# 03_-_Power.net
KiCad netlist of a schematic drawn in Altium Designer
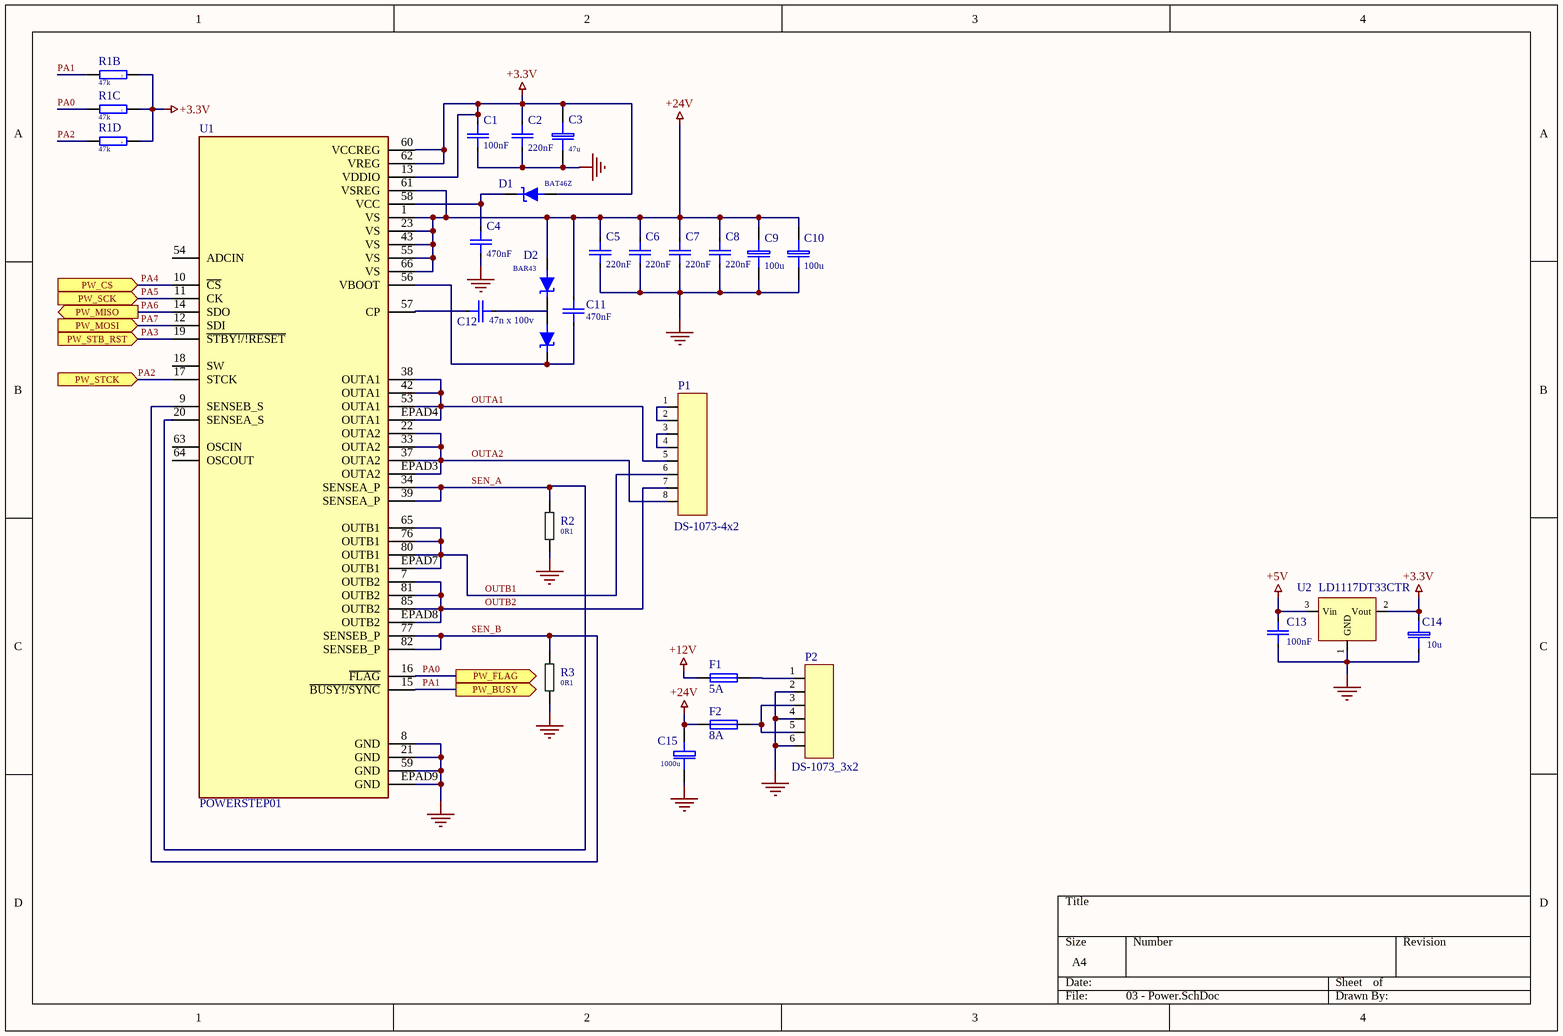
[diagram p0: 03 - Power.SchDoc]

(export (version "E")
  (design (tool "Eeschema 10.0.6"))
  (components
    (comp (ref "C1")
      (value "100nF")
      (footprint "CAP: 0805")
      (description "SMD-0805")
      (libsource (lib "RCL_SMD_Integrated_Library") (part "C-0805"))
    )
    (comp (ref "C2")
      (value "220nF")
      (footprint "CAP: 0805")
      (description "SMD-0805")
      (libsource (lib "RCL_SMD_Integrated_Library") (part "C-0805"))
    )
    (comp (ref "C3")
      (value "47u")
      (footprint "EL SMD Case C D5x5.3 h5.4(0505)")
      (description "EL 50V SMD Case C D5x5.3 h5.4")
      (libsource (lib "SMD-RCL") (part "EL 10u/50V"))
    )
    (comp (ref "C4")
      (value "470nF")
      (footprint "CAP: 0805")
      (description "SMD-0805")
      (libsource (lib "RCL_SMD_Integrated_Library") (part "C-0805"))
    )
    (comp (ref "C5")
      (value "220nF")
      (footprint "CAP: 0805")
      (description "SMD-0805")
      (libsource (lib "RCL_SMD_Integrated_Library") (part "C-0805"))
    )
    (comp (ref "C6")
      (value "220nF")
      (footprint "CAP: 0805")
      (description "SMD-0805")
      (libsource (lib "RCL_SMD_Integrated_Library") (part "C-0805"))
    )
    (comp (ref "C7")
      (value "220nF")
      (footprint "CAP: 0805")
      (description "SMD-0805")
      (libsource (lib "RCL_SMD_Integrated_Library") (part "C-0805"))
    )
    (comp (ref "C8")
      (value "220nF")
      (footprint "CAP: 0805")
      (description "SMD-0805")
      (libsource (lib "RCL_SMD_Integrated_Library") (part "C-0805"))
    )
    (comp (ref "C9")
      (value "100u")
      (footprint "EL SMD Case G D10x10.3 h10.2(1010)")
      (description "EL 35V SMD Case G D10x10.3h10.5")
      (libsource (lib "SMD-RCL") (part "EL 100u/35V"))
    )
    (comp (ref "C10")
      (value "100u")
      (footprint "EL SMD Case G D10x10.3 h10.2(1010)")
      (description "EL 35V SMD Case G D10x10.3h10.5")
      (libsource (lib "SMD-RCL") (part "EL 100u/35V"))
    )
    (comp (ref "C11")
      (value "470nF")
      (footprint "CAP: 0805")
      (description "SMD-0805")
      (libsource (lib "RCL_SMD_Integrated_Library") (part "C-0805"))
    )
    (comp (ref "C12")
      (value "47n x 100v")
      (footprint "CAP: 0805")
      (description "SMD-0805")
      (libsource (lib "RCL_SMD_Integrated_Library") (part "C-0805"))
    )
    (comp (ref "C13")
      (value "100nF")
      (footprint "CAP: 0805")
      (description "SMD-0805")
      (libsource (lib "RCL_SMD_Integrated_Library") (part "C-0805"))
    )
    (comp (ref "C14")
      (value "10u")
      (footprint "EL Case A (3216-18)")
      (description "El Case A (2012-12)")
      (libsource (lib "RCL_SMD_Integrated_Library") (part "EL 10u/16V Tant."))
    )
    (comp (ref "C15")
      (value "1000u")
      (footprint "El-d13-h21-F5.08")
      (description "35V 105C 34m 1.8A 5000h")
      (libsource (lib "Cap-El") (part "1000u-35V 105F"))
    )
    (comp (ref "D1")
      (value "BAT46Z")
      (footprint "SOD123")
      (description "SMD-SOT123 60V 15mA 2.2pF 1nS")
      (libsource (lib "Diodes") (part "1N6263"))
    )
    (comp (ref "D2")
      (value "BAR43")
      (footprint "SOT23")
      (description "SMD-SOT23 30V 0.2A 5nS 10pF")
      (libsource (lib "Diodes") (part "BAT54S"))
    )
    (comp (ref "F1")
      (value "5A")
      (footprint "Littelfuse 0451/453")
      (description "0451003")
      (libsource (lib "stm32_Integrated_Library") (part "Littelfuse 0451"))
    )
    (comp (ref "F2")
      (value "8A")
      (footprint "Littelfuse 0451/453")
      (description "0451003")
      (libsource (lib "stm32_Integrated_Library") (part "Littelfuse 0451"))
    )
    (comp (ref "P1")
      (value "DS-1073-4x2")
      (footprint "DS-1073-4x2")
      (libsource (lib "stm32_Integrated_Library") (part "DS-1073-4x2"))
    )
    (comp (ref "P2")
      (value "DS-1073_3x2")
      (footprint "DS-1073-2x3")
      (libsource (lib "stm32_Integrated_Library") (part "DS-1073_3x2"))
    )
    (comp (ref "R1")
      (value "47k")
      (footprint "RM4x0603")
      (description "SMD 4RM-0603 1\\16W 5%")
      (libsource (lib "SMD-RCL") (part "4RM-0603"))
    )
    (comp (ref "R2")
      (value "0R1")
      (footprint "R2512")
      (description "SMD 2512 1W 5% 200V")
      (libsource (lib "SMD-RCL") (part "R-2512"))
    )
    (comp (ref "R3")
      (value "0R1")
      (footprint "R2512")
      (description "SMD 2512 1W 5% 200V")
      (libsource (lib "SMD-RCL") (part "R-2512"))
    )
    (comp (ref "U1")
      (value "POWERSTEP01")
      (footprint "POWERSTEP01")
      (description "Bipolar Motor Driver Power MOSFET SPI 89-VFQFPN _11x14_")
      (fields (field (name "MF") "STMicroelectronics"))
      (libsource (lib "stm32_Integrated_Library") (part "POWERSTEP01"))
    )
    (comp (ref "U2")
      (value "LD1117DT33CTR")
      (footprint "DPAK")
      (libsource (lib "stm32_Integrated_Library") (part "LD1117DT33CTR"))
    )
  )
  (nets
    (net (code "1") (name "+3.3V") (class "Default")
      (node (ref "C1") (pin "2") (pinfunction "2_2") (pintype "passive"))
      (node (ref "C14") (pin "1") (pinfunction "1_1") (pintype "passive"))
      (node (ref "C2") (pin "1") (pinfunction "1_1") (pintype "passive"))
      (node (ref "C3") (pin "1") (pinfunction "+_1") (pintype "passive"))
      (node (ref "D1") (pin "1") (pinfunction "A_1") (pintype "passive"))
      (node (ref "R1") (pin "2") (pinfunction "2_2") (pintype "passive"))
      (node (ref "R1") (pin "3") (pinfunction "3_3") (pintype "passive"))
      (node (ref "R1") (pin "4") (pinfunction "4_4") (pintype "passive"))
      (node (ref "U1") (pin "13") (pinfunction "VDDIO_13") (pintype "power_in"))
      (node (ref "U1") (pin "60") (pinfunction "VCCREG_60") (pintype "power_in"))
      (node (ref "U1") (pin "62") (pinfunction "VREG_62") (pintype "power_in"))
      (node (ref "U2") (pin "2") (pinfunction "Vout_2") (pintype "passive"))
    )
    (net (code "2") (name "+5V") (class "Default")
      (node (ref "C13") (pin "2") (pinfunction "2_2") (pintype "passive"))
      (node (ref "U2") (pin "3") (pinfunction "Vin_3") (pintype "passive"))
    )
    (net (code "3") (name "+12V") (class "Default")
      (node (ref "F1") (pin "1") (pinfunction "1_1") (pintype "passive"))
    )
    (net (code "4") (name "+24V") (class "Default")
      (node (ref "C10") (pin "1") (pinfunction "1_1") (pintype "passive"))
      (node (ref "C11") (pin "1") (pinfunction "1_1") (pintype "passive"))
      (node (ref "C15") (pin "1") (pinfunction "1_1") (pintype "passive"))
      (node (ref "C5") (pin "1") (pinfunction "1_1") (pintype "passive"))
      (node (ref "C6") (pin "1") (pinfunction "1_1") (pintype "passive"))
      (node (ref "C7") (pin "1") (pinfunction "1_1") (pintype "passive"))
      (node (ref "C8") (pin "1") (pinfunction "1_1") (pintype "passive"))
      (node (ref "C9") (pin "1") (pinfunction "1_1") (pintype "passive"))
      (node (ref "D2") (pin "1") (pinfunction "1_1") (pintype "passive"))
      (node (ref "F2") (pin "1") (pinfunction "1_1") (pintype "passive"))
      (node (ref "U1") (pin "1") (pinfunction "VS_1") (pintype "passive"))
      (node (ref "U1") (pin "23") (pinfunction "VS_23") (pintype "passive"))
      (node (ref "U1") (pin "43") (pinfunction "VS_43") (pintype "passive"))
      (node (ref "U1") (pin "55") (pinfunction "VS_55") (pintype "passive"))
      (node (ref "U1") (pin "61") (pinfunction "VSREG_61") (pintype "passive"))
      (node (ref "U1") (pin "66") (pinfunction "VS_66") (pintype "passive"))
    )
    (net (code "5") (name "/OUTA1") (class "Default")
      (node (ref "P1") (pin "5") (pintype "passive"))
      (node (ref "U1") (pin "38") (pinfunction "OUTA1_38") (pintype "power_in"))
      (node (ref "U1") (pin "42") (pinfunction "OUTA1_42") (pintype "power_in"))
      (node (ref "U1") (pin "53") (pinfunction "OUTA1_53") (pintype "power_in"))
      (node (ref "U1") (pin "EPAD4") (pinfunction "OUTA1_EPAD4") (pintype "power_in"))
    )
    (net (code "6") (name "/OUTA2") (class "Default")
      (node (ref "P1") (pin "8") (pintype "passive"))
      (node (ref "U1") (pin "22") (pinfunction "OUTA2_22") (pintype "power_in"))
      (node (ref "U1") (pin "33") (pinfunction "OUTA2_33") (pintype "power_in"))
      (node (ref "U1") (pin "37") (pinfunction "OUTA2_37") (pintype "power_in"))
      (node (ref "U1") (pin "EPAD3") (pinfunction "OUTA2_EPAD3") (pintype "power_in"))
    )
    (net (code "7") (name "/OUTB1") (class "Default")
      (node (ref "P1") (pin "6") (pintype "passive"))
      (node (ref "U1") (pin "65") (pinfunction "OUTB1_65") (pintype "power_in"))
      (node (ref "U1") (pin "76") (pinfunction "OUTB1_76") (pintype "power_in"))
      (node (ref "U1") (pin "80") (pinfunction "OUTB1_80") (pintype "power_in"))
      (node (ref "U1") (pin "EPAD7") (pinfunction "OUTB1_EPAD7") (pintype "power_in"))
    )
    (net (code "8") (name "/OUTB2") (class "Default")
      (node (ref "P1") (pin "7") (pintype "passive"))
      (node (ref "U1") (pin "7") (pinfunction "OUTB2_7") (pintype "power_in"))
      (node (ref "U1") (pin "81") (pinfunction "OUTB2_81") (pintype "power_in"))
      (node (ref "U1") (pin "85") (pinfunction "OUTB2_85") (pintype "power_in"))
      (node (ref "U1") (pin "EPAD8") (pinfunction "OUTB2_EPAD8") (pintype "power_in"))
    )
    (net (code "9") (name "/PA0") (class "Default")
      (node (ref "R1") (pin "6") (pinfunction "6_6") (pintype "passive"))
      (node (ref "U1") (pin "16") (pinfunction "~{FLAG}_16") (pintype "passive"))
    )
    (net (code "10") (name "/PA1") (class "Default")
      (node (ref "R1") (pin "7") (pinfunction "7_7") (pintype "passive"))
      (node (ref "U1") (pin "15") (pinfunction "~{BUSY!/SYNC}_15") (pintype "passive"))
    )
    (net (code "11") (name "/PA2") (class "Default")
      (node (ref "R1") (pin "5") (pinfunction "5_5") (pintype "passive"))
      (node (ref "U1") (pin "17") (pinfunction "STCK_17") (pintype "passive"))
    )
    (net (code "12") (name "/PA3") (class "Default")
      (node (ref "U1") (pin "19") (pinfunction "~{STBY!/!RESET}_19") (pintype "passive"))
    )
    (net (code "13") (name "/PA4") (class "Default")
      (node (ref "U1") (pin "10") (pinfunction "~{CS}_10") (pintype "passive"))
    )
    (net (code "14") (name "/PA5") (class "Default")
      (node (ref "U1") (pin "11") (pinfunction "CK_11") (pintype "passive"))
    )
    (net (code "15") (name "/PA6") (class "Default")
      (node (ref "U1") (pin "14") (pinfunction "SDO_14") (pintype "passive"))
    )
    (net (code "16") (name "/PA7") (class "Default")
      (node (ref "U1") (pin "12") (pinfunction "SDI_12") (pintype "passive"))
    )
    (net (code "17") (name "/SEN_A") (class "Default")
      (node (ref "R2") (pin "2") (pinfunction "2_2") (pintype "passive"))
      (node (ref "U1") (pin "20") (pinfunction "SENSEA_S_20") (pintype "passive"))
      (node (ref "U1") (pin "34") (pinfunction "SENSEA_P_34") (pintype "passive"))
      (node (ref "U1") (pin "39") (pinfunction "SENSEA_P_39") (pintype "passive"))
    )
    (net (code "18") (name "/SEN_B") (class "Default")
      (node (ref "R3") (pin "2") (pinfunction "2_2") (pintype "passive"))
      (node (ref "U1") (pin "77") (pinfunction "SENSEB_P_77") (pintype "passive"))
      (node (ref "U1") (pin "82") (pinfunction "SENSEB_P_82") (pintype "passive"))
      (node (ref "U1") (pin "9") (pinfunction "SENSEB_S_9") (pintype "passive"))
    )
    (net (code "19") (name "GND") (class "Default")
      (node (ref "C1") (pin "1") (pinfunction "1_1") (pintype "passive"))
      (node (ref "C10") (pin "2") (pinfunction "2_2") (pintype "passive"))
      (node (ref "C13") (pin "1") (pinfunction "1_1") (pintype "passive"))
      (node (ref "C14") (pin "2") (pinfunction "2_2") (pintype "passive"))
      (node (ref "C15") (pin "2") (pinfunction "2_2") (pintype "passive"))
      (node (ref "C2") (pin "2") (pinfunction "2_2") (pintype "passive"))
      (node (ref "C3") (pin "2") (pinfunction "-_2") (pintype "passive"))
      (node (ref "C4") (pin "2") (pinfunction "2_2") (pintype "passive"))
      (node (ref "C5") (pin "2") (pinfunction "2_2") (pintype "passive"))
      (node (ref "C6") (pin "2") (pinfunction "2_2") (pintype "passive"))
      (node (ref "C7") (pin "2") (pinfunction "2_2") (pintype "passive"))
      (node (ref "C8") (pin "2") (pinfunction "2_2") (pintype "passive"))
      (node (ref "C9") (pin "2") (pinfunction "2_2") (pintype "passive"))
      (node (ref "P2") (pin "2") (pintype "passive"))
      (node (ref "P2") (pin "4") (pintype "passive"))
      (node (ref "P2") (pin "6") (pintype "passive"))
      (node (ref "R2") (pin "1") (pinfunction "1_1") (pintype "passive"))
      (node (ref "R3") (pin "1") (pinfunction "1_1") (pintype "passive"))
      (node (ref "U1") (pin "21") (pinfunction "GND_21") (pintype "power_in"))
      (node (ref "U1") (pin "59") (pinfunction "GND_59") (pintype "power_in"))
      (node (ref "U1") (pin "8") (pinfunction "GND_8") (pintype "power_in"))
      (node (ref "U1") (pin "EPAD9") (pinfunction "GND_EPAD9") (pintype "power_in"))
      (node (ref "U2") (pin "1") (pinfunction "GND_1") (pintype "passive"))
    )
    (net (code "20") (name "Net-(C12-Pad2)") (class "Default")
      (node (ref "C12") (pin "2") (pinfunction "2_2") (pintype "passive"))
      (node (ref "D2") (pin "3") (pinfunction "3_3") (pintype "passive"))
    )
    (net (code "21") (name "Net-(D1-C)") (class "Default")
      (node (ref "C4") (pin "1") (pinfunction "1_1") (pintype "passive"))
      (node (ref "D1") (pin "2") (pinfunction "C_2") (pintype "passive"))
      (node (ref "U1") (pin "58") (pinfunction "VCC_58") (pintype "power_in"))
    )
    (net (code "22") (name "Net-(F1-Pad2)") (class "Default")
      (node (ref "F1") (pin "2") (pinfunction "2_2") (pintype "passive"))
      (node (ref "P2") (pin "1") (pintype "passive"))
    )
    (net (code "23") (name "Net-(F2-Pad2)") (class "Default")
      (node (ref "F2") (pin "2") (pinfunction "2_2") (pintype "passive"))
      (node (ref "P2") (pin "3") (pintype "passive"))
      (node (ref "P2") (pin "5") (pintype "passive"))
    )
    (net (code "24") (name "Net-(P1-Pad1)") (class "Default")
      (node (ref "P1") (pin "1") (pintype "passive"))
      (node (ref "P1") (pin "2") (pintype "passive"))
    )
    (net (code "25") (name "Net-(P1-Pad3)") (class "Default")
      (node (ref "P1") (pin "3") (pintype "passive"))
      (node (ref "P1") (pin "4") (pintype "passive"))
    )
    (net (code "26") (name "Net-(U1-CP)") (class "Default")
      (node (ref "C12") (pin "1") (pinfunction "1_1") (pintype "passive"))
      (node (ref "U1") (pin "57") (pinfunction "CP_57") (pintype "passive"))
    )
    (net (code "27") (name "Net-(U1-VBOOT)") (class "Default")
      (node (ref "C11") (pin "2") (pinfunction "2_2") (pintype "passive"))
      (node (ref "D2") (pin "2") (pinfunction "2_2") (pintype "passive"))
      (node (ref "U1") (pin "56") (pinfunction "VBOOT_56") (pintype "power_in"))
    )
    (net (code "28") (name "unconnected-(U1-ADCIN-Pad54)") (class "Default")
      (node (ref "U1") (pin "54") (pinfunction "ADCIN_54") (pintype "passive"))
    )
    (net (code "29") (name "unconnected-(U1-OSCIN-Pad63)") (class "Default")
      (node (ref "U1") (pin "63") (pinfunction "OSCIN_63") (pintype "passive"))
    )
    (net (code "30") (name "unconnected-(U1-OSCOUT-Pad64)") (class "Default")
      (node (ref "U1") (pin "64") (pinfunction "OSCOUT_64") (pintype "passive"))
    )
    (net (code "31") (name "unconnected-(U1-SW-Pad18)") (class "Default")
      (node (ref "U1") (pin "18") (pinfunction "SW_18") (pintype "passive"))
    )
  )
)
